# Power_Supply.net
KiCad netlist of a schematic drawn in Altium Designer
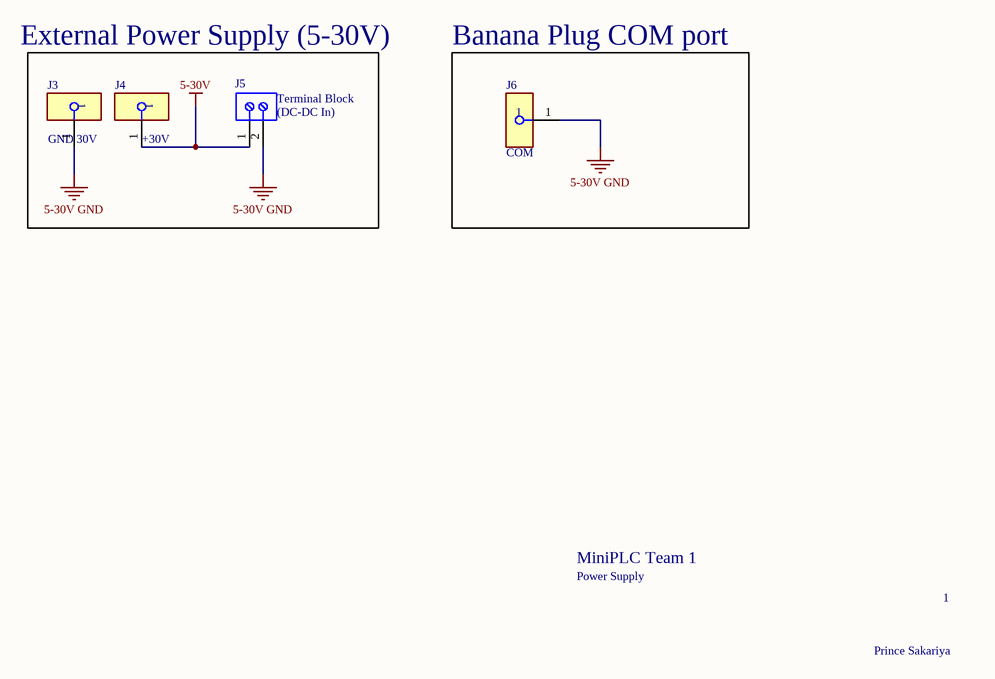
[diagram p0: Power Supply.SchDoc]

(export (version "E")
  (design (tool "Eeschema 10.0.6"))
  (components
    (comp (ref "J3")
      (value "GND 30V")
      (footprint "FP-1581-5-MFG")
      (description "CONN BANANA JACK TURRET GREEN")
      (libsource (lib "") (part "c5c826e0c4b67fe3b42ef77f2d4decc_1"))
    )
    (comp (ref "J4")
      (value "+30V")
      (footprint "FP-1581-5-MFG")
      (description "CONN BANANA JACK TURRET GREEN")
      (libsource (lib "") (part "c5c826e0c4b67fe3b42ef77f2d4decc_1"))
    )
    (comp (ref "J5")
      (value "Terminal Block")
      (footprint "691103110002")
      (fields (field (name "VOLTAGE") "125V"))
      (libsource (lib "Altium Content Vault") (part "TBL - 1R - 02P - Screw"))
    )
    (comp (ref "J6")
      (value "COM")
      (footprint "FP-1581-5-MFG")
      (description "CONN BANANA JACK TURRET GREEN")
      (libsource (lib "Altium Content Vault") (part "c5c826e0c4b67fe3b42ef77f2d4decc"))
    )
  )
  (nets
    (net (code "1") (name "5-30V") (class "Default")
      (node (ref "J4") (pin "1") (pinfunction "1_1") (pintype "passive"))
      (node (ref "J5") (pin "1") (pinfunction "1_1") (pintype "passive"))
    )
    (net (code "2") (name "5-30V GND") (class "Default")
      (node (ref "J3") (pin "1") (pinfunction "1_1") (pintype "passive"))
      (node (ref "J5") (pin "2") (pinfunction "2_2") (pintype "passive"))
      (node (ref "J6") (pin "1") (pinfunction "1_1") (pintype "passive"))
    )
  )
)
